# pcie_power.net
KiCad netlist of a schematic drawn in Altium Designer
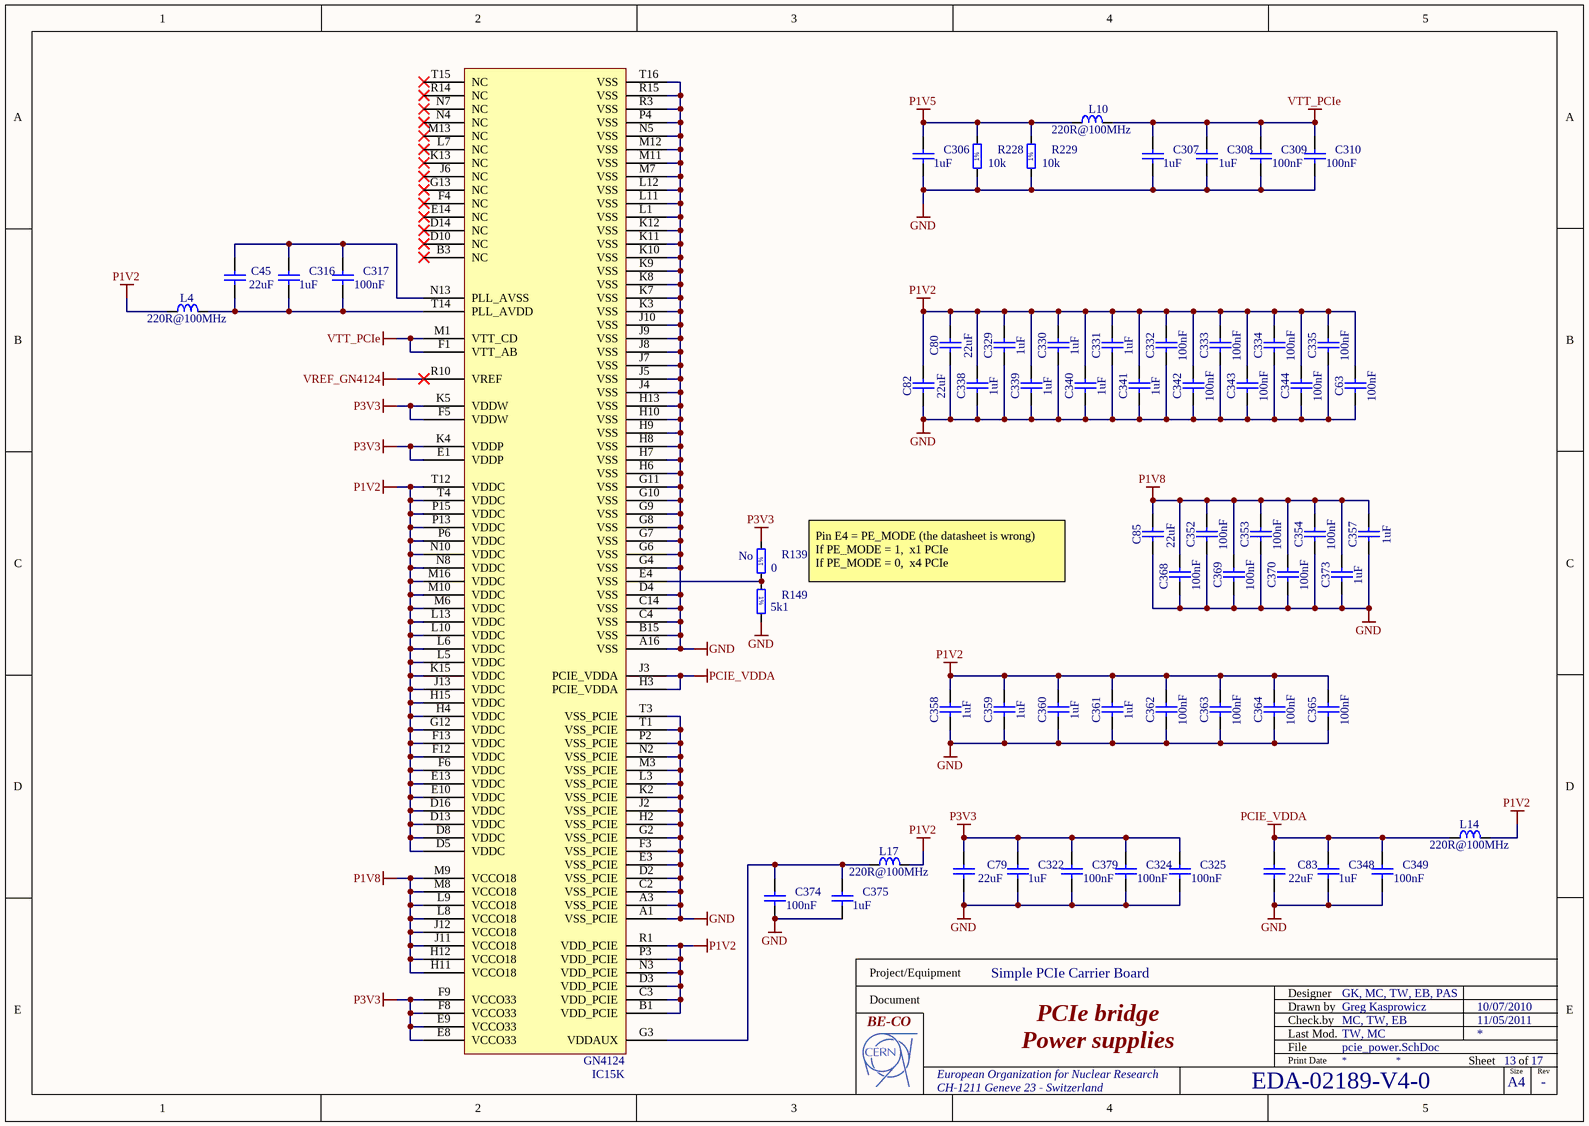
[diagram p0: pcie_power.SchDoc]

(export (version "E")
  (design (tool "Eeschema 10.0.6"))
  (components
    (comp (ref "C45")
      (value "22uF")
      (footprint "CAPC3216X180N")
      (description "Non-polarised capacitor")
      (fields
        (field (name "PART NUMBER") "CC1206_22UF_10V_10%_X7R")
        (field (name "VOLTAGE") "10V")
        (field (name "AUTHOR") "CERN DEM JLC")
      )
      (libsource (lib "Capacitors") (part "Capacitor - non polarized"))
    )
    (comp (ref "C63")
      (value "100nF")
      (footprint "CAPC1005X55N")
      (description "Non-polarised capacitor")
      (fields
        (field (name "PART NUMBER") "CC0402_100NF_16V_10%_X7R")
        (field (name "VOLTAGE") "16V")
        (field (name "AUTHOR") "CERN DEM JLC")
      )
      (libsource (lib "Capacitors") (part "Capacitor - non polarized"))
    )
    (comp (ref "C79")
      (value "22uF")
      (footprint "CAPC3216X180N")
      (description "Non-polarised capacitor")
      (fields
        (field (name "PART NUMBER") "CC1206_22UF_10V_10%_X7R")
        (field (name "VOLTAGE") "10V")
        (field (name "AUTHOR") "CERN DEM JLC")
      )
      (libsource (lib "Capacitors") (part "Capacitor - non polarized"))
    )
    (comp (ref "C80")
      (value "22uF")
      (footprint "CAPC3216X180N")
      (description "Non-polarised capacitor")
      (fields
        (field (name "PART NUMBER") "CC1206_22UF_10V_10%_X7R")
        (field (name "VOLTAGE") "10V")
        (field (name "AUTHOR") "CERN DEM JLC")
      )
      (libsource (lib "Capacitors") (part "Capacitor - non polarized"))
    )
    (comp (ref "C82")
      (value "22uF")
      (footprint "CAPC3216X180N")
      (description "Non-polarised capacitor")
      (fields
        (field (name "PART NUMBER") "CC1206_22UF_10V_10%_X7R")
        (field (name "VOLTAGE") "10V")
        (field (name "AUTHOR") "CERN DEM JLC")
      )
      (libsource (lib "Capacitors") (part "Capacitor - non polarized"))
    )
    (comp (ref "C83")
      (value "22uF")
      (footprint "CAPC3216X180N")
      (description "Non-polarised capacitor")
      (fields
        (field (name "PART NUMBER") "CC1206_22UF_10V_10%_X7R")
        (field (name "VOLTAGE") "10V")
        (field (name "AUTHOR") "CERN DEM JLC")
      )
      (libsource (lib "Capacitors") (part "Capacitor - non polarized"))
    )
    (comp (ref "C85")
      (value "22uF")
      (footprint "CAPC3216X180N")
      (description "Non-polarised capacitor")
      (fields
        (field (name "PART NUMBER") "CC1206_22UF_10V_10%_X7R")
        (field (name "VOLTAGE") "10V")
        (field (name "AUTHOR") "CERN DEM JLC")
      )
      (libsource (lib "Capacitors") (part "Capacitor - non polarized"))
    )
    (comp (ref "C306")
      (value "1uF")
      (footprint "CAPC1608X87N")
      (description "Non-polarised capacitor")
      (fields
        (field (name "PART NUMBER") "CC0603_1UF_16V_10%_X7R")
        (field (name "VOLTAGE") "16V")
        (field (name "AUTHOR") "CERN DEM JLC")
      )
      (libsource (lib "Capacitors") (part "Capacitor - non polarized"))
    )
    (comp (ref "C307")
      (value "1uF")
      (footprint "CAPC1608X87N")
      (description "Non-polarised capacitor")
      (fields
        (field (name "PART NUMBER") "CC0603_1UF_16V_10%_X7R")
        (field (name "VOLTAGE") "16V")
        (field (name "AUTHOR") "CERN DEM JLC")
      )
      (libsource (lib "Capacitors") (part "Capacitor - non polarized"))
    )
    (comp (ref "C308")
      (value "1uF")
      (footprint "CAPC1608X87N")
      (description "Non-polarised capacitor")
      (fields
        (field (name "PART NUMBER") "CC0603_1UF_16V_10%_X7R")
        (field (name "VOLTAGE") "16V")
        (field (name "AUTHOR") "CERN DEM JLC")
      )
      (libsource (lib "Capacitors") (part "Capacitor - non polarized"))
    )
    (comp (ref "C309")
      (value "100nF")
      (footprint "CAPC1005X55N")
      (description "Non-polarised capacitor")
      (fields
        (field (name "PART NUMBER") "CC0402_100NF_16V_10%_X7R")
        (field (name "VOLTAGE") "16V")
        (field (name "AUTHOR") "CERN DEM JLC")
      )
      (libsource (lib "Capacitors") (part "Capacitor - non polarized"))
    )
    (comp (ref "C310")
      (value "100nF")
      (footprint "CAPC1005X55N")
      (description "Non-polarised capacitor")
      (fields
        (field (name "PART NUMBER") "CC0402_100NF_16V_10%_X7R")
        (field (name "VOLTAGE") "16V")
        (field (name "AUTHOR") "CERN DEM JLC")
      )
      (libsource (lib "Capacitors") (part "Capacitor - non polarized"))
    )
    (comp (ref "C316")
      (value "1uF")
      (footprint "CAPC1608X87N")
      (description "Non-polarised capacitor")
      (fields
        (field (name "PART NUMBER") "CC0603_1UF_16V_10%_X7R")
        (field (name "VOLTAGE") "16V")
        (field (name "AUTHOR") "CERN DEM JLC")
      )
      (libsource (lib "Capacitors") (part "Capacitor - non polarized"))
    )
    (comp (ref "C317")
      (value "100nF")
      (footprint "CAPC1005X55N")
      (description "Non-polarised capacitor")
      (fields
        (field (name "PART NUMBER") "CC0402_100NF_16V_10%_X7R")
        (field (name "VOLTAGE") "16V")
        (field (name "AUTHOR") "CERN DEM JLC")
      )
      (libsource (lib "Capacitors") (part "Capacitor - non polarized"))
    )
    (comp (ref "C322")
      (value "1uF")
      (footprint "CAPC1608X87N")
      (description "Non-polarised capacitor")
      (fields
        (field (name "PART NUMBER") "CC0603_1UF_16V_10%_X7R")
        (field (name "VOLTAGE") "16V")
        (field (name "AUTHOR") "CERN DEM JLC")
      )
      (libsource (lib "Capacitors") (part "Capacitor - non polarized"))
    )
    (comp (ref "C324")
      (value "100nF")
      (footprint "CAPC1005X55N")
      (description "Non-polarised capacitor")
      (fields
        (field (name "PART NUMBER") "CC0402_100NF_16V_10%_X7R")
        (field (name "VOLTAGE") "16V")
        (field (name "AUTHOR") "CERN DEM JLC")
      )
      (libsource (lib "Capacitors") (part "Capacitor - non polarized"))
    )
    (comp (ref "C325")
      (value "100nF")
      (footprint "CAPC1005X55N")
      (description "Non-polarised capacitor")
      (fields
        (field (name "PART NUMBER") "CC0402_100NF_16V_10%_X7R")
        (field (name "VOLTAGE") "16V")
        (field (name "AUTHOR") "CERN DEM JLC")
      )
      (libsource (lib "Capacitors") (part "Capacitor - non polarized"))
    )
    (comp (ref "C329")
      (value "1uF")
      (footprint "CAPC1608X87N")
      (description "Non-polarised capacitor")
      (fields
        (field (name "PART NUMBER") "CC0603_1UF_16V_10%_X7R")
        (field (name "VOLTAGE") "16V")
        (field (name "AUTHOR") "CERN DEM JLC")
      )
      (libsource (lib "Capacitors") (part "Capacitor - non polarized"))
    )
    (comp (ref "C330")
      (value "1uF")
      (footprint "CAPC1608X87N")
      (description "Non-polarised capacitor")
      (fields
        (field (name "PART NUMBER") "CC0603_1UF_16V_10%_X7R")
        (field (name "VOLTAGE") "16V")
        (field (name "AUTHOR") "CERN DEM JLC")
      )
      (libsource (lib "Capacitors") (part "Capacitor - non polarized"))
    )
    (comp (ref "C331")
      (value "1uF")
      (footprint "CAPC1608X87N")
      (description "Non-polarised capacitor")
      (fields
        (field (name "PART NUMBER") "CC0603_1UF_16V_10%_X7R")
        (field (name "VOLTAGE") "16V")
        (field (name "AUTHOR") "CERN DEM JLC")
      )
      (libsource (lib "Capacitors") (part "Capacitor - non polarized"))
    )
    (comp (ref "C332")
      (value "100nF")
      (footprint "CAPC1005X55N")
      (description "Non-polarised capacitor")
      (fields
        (field (name "PART NUMBER") "CC0402_100NF_16V_10%_X7R")
        (field (name "VOLTAGE") "16V")
        (field (name "AUTHOR") "CERN DEM JLC")
      )
      (libsource (lib "Capacitors") (part "Capacitor - non polarized"))
    )
    (comp (ref "C333")
      (value "100nF")
      (footprint "CAPC1005X55N")
      (description "Non-polarised capacitor")
      (fields
        (field (name "PART NUMBER") "CC0402_100NF_16V_10%_X7R")
        (field (name "VOLTAGE") "16V")
        (field (name "AUTHOR") "CERN DEM JLC")
      )
      (libsource (lib "Capacitors") (part "Capacitor - non polarized"))
    )
    (comp (ref "C334")
      (value "100nF")
      (footprint "CAPC1005X55N")
      (description "Non-polarised capacitor")
      (fields
        (field (name "PART NUMBER") "CC0402_100NF_16V_10%_X7R")
        (field (name "VOLTAGE") "16V")
        (field (name "AUTHOR") "CERN DEM JLC")
      )
      (libsource (lib "Capacitors") (part "Capacitor - non polarized"))
    )
    (comp (ref "C335")
      (value "100nF")
      (footprint "CAPC1005X55N")
      (description "Non-polarised capacitor")
      (fields
        (field (name "PART NUMBER") "CC0402_100NF_16V_10%_X7R")
        (field (name "VOLTAGE") "16V")
        (field (name "AUTHOR") "CERN DEM JLC")
      )
      (libsource (lib "Capacitors") (part "Capacitor - non polarized"))
    )
    (comp (ref "C338")
      (value "1uF")
      (footprint "CAPC1608X87N")
      (description "Non-polarised capacitor")
      (fields
        (field (name "PART NUMBER") "CC0603_1UF_16V_10%_X7R")
        (field (name "VOLTAGE") "16V")
        (field (name "AUTHOR") "CERN DEM JLC")
      )
      (libsource (lib "Capacitors") (part "Capacitor - non polarized"))
    )
    (comp (ref "C339")
      (value "1uF")
      (footprint "CAPC1608X87N")
      (description "Non-polarised capacitor")
      (fields
        (field (name "PART NUMBER") "CC0603_1UF_16V_10%_X7R")
        (field (name "VOLTAGE") "16V")
        (field (name "AUTHOR") "CERN DEM JLC")
      )
      (libsource (lib "Capacitors") (part "Capacitor - non polarized"))
    )
    (comp (ref "C340")
      (value "1uF")
      (footprint "CAPC1608X87N")
      (description "Non-polarised capacitor")
      (fields
        (field (name "PART NUMBER") "CC0603_1UF_16V_10%_X7R")
        (field (name "VOLTAGE") "16V")
        (field (name "AUTHOR") "CERN DEM JLC")
      )
      (libsource (lib "Capacitors") (part "Capacitor - non polarized"))
    )
    (comp (ref "C341")
      (value "1uF")
      (footprint "CAPC1608X87N")
      (description "Non-polarised capacitor")
      (fields
        (field (name "PART NUMBER") "CC0603_1UF_16V_10%_X7R")
        (field (name "VOLTAGE") "16V")
        (field (name "AUTHOR") "CERN DEM JLC")
      )
      (libsource (lib "Capacitors") (part "Capacitor - non polarized"))
    )
    (comp (ref "C342")
      (value "100nF")
      (footprint "CAPC1005X55N")
      (description "Non-polarised capacitor")
      (fields
        (field (name "PART NUMBER") "CC0402_100NF_16V_10%_X7R")
        (field (name "VOLTAGE") "16V")
        (field (name "AUTHOR") "CERN DEM JLC")
      )
      (libsource (lib "Capacitors") (part "Capacitor - non polarized"))
    )
    (comp (ref "C343")
      (value "100nF")
      (footprint "CAPC1005X55N")
      (description "Non-polarised capacitor")
      (fields
        (field (name "PART NUMBER") "CC0402_100NF_16V_10%_X7R")
        (field (name "VOLTAGE") "16V")
        (field (name "AUTHOR") "CERN DEM JLC")
      )
      (libsource (lib "Capacitors") (part "Capacitor - non polarized"))
    )
    (comp (ref "C344")
      (value "100nF")
      (footprint "CAPC1005X55N")
      (description "Non-polarised capacitor")
      (fields
        (field (name "PART NUMBER") "CC0402_100NF_16V_10%_X7R")
        (field (name "VOLTAGE") "16V")
        (field (name "AUTHOR") "CERN DEM JLC")
      )
      (libsource (lib "Capacitors") (part "Capacitor - non polarized"))
    )
    (comp (ref "C348")
      (value "1uF")
      (footprint "CAPC1608X87N")
      (description "Non-polarised capacitor")
      (fields
        (field (name "PART NUMBER") "CC0603_1UF_16V_10%_X7R")
        (field (name "VOLTAGE") "16V")
        (field (name "AUTHOR") "CERN DEM JLC")
      )
      (libsource (lib "Capacitors") (part "Capacitor - non polarized"))
    )
    (comp (ref "C349")
      (value "100nF")
      (footprint "CAPC1005X55N")
      (description "Non-polarised capacitor")
      (fields
        (field (name "PART NUMBER") "CC0402_100NF_16V_10%_X7R")
        (field (name "VOLTAGE") "16V")
        (field (name "AUTHOR") "CERN DEM JLC")
      )
      (libsource (lib "Capacitors") (part "Capacitor - non polarized"))
    )
    (comp (ref "C352")
      (value "100nF")
      (footprint "CAPC1005X55N")
      (description "Non-polarised capacitor")
      (fields
        (field (name "PART NUMBER") "CC0402_100NF_16V_10%_X7R")
        (field (name "VOLTAGE") "16V")
        (field (name "AUTHOR") "CERN DEM JLC")
      )
      (libsource (lib "Capacitors") (part "Capacitor - non polarized"))
    )
    (comp (ref "C353")
      (value "100nF")
      (footprint "CAPC1005X55N")
      (description "Non-polarised capacitor")
      (fields
        (field (name "PART NUMBER") "CC0402_100NF_16V_10%_X7R")
        (field (name "VOLTAGE") "16V")
        (field (name "AUTHOR") "CERN DEM JLC")
      )
      (libsource (lib "Capacitors") (part "Capacitor - non polarized"))
    )
    (comp (ref "C354")
      (value "100nF")
      (footprint "CAPC1005X55N")
      (description "Non-polarised capacitor")
      (fields
        (field (name "PART NUMBER") "CC0402_100NF_16V_10%_X7R")
        (field (name "VOLTAGE") "16V")
        (field (name "AUTHOR") "CERN DEM JLC")
      )
      (libsource (lib "Capacitors") (part "Capacitor - non polarized"))
    )
    (comp (ref "C357")
      (value "1uF")
      (footprint "CAPC1608X87N")
      (description "Non-polarised capacitor")
      (fields
        (field (name "PART NUMBER") "CC0603_1UF_16V_10%_X7R")
        (field (name "VOLTAGE") "16V")
        (field (name "AUTHOR") "CERN DEM JLC")
      )
      (libsource (lib "Capacitors") (part "Capacitor - non polarized"))
    )
    (comp (ref "C358")
      (value "1uF")
      (footprint "CAPC1608X87N")
      (description "Non-polarised capacitor")
      (fields
        (field (name "PART NUMBER") "CC0603_1UF_16V_10%_X7R")
        (field (name "VOLTAGE") "16V")
        (field (name "AUTHOR") "CERN DEM JLC")
      )
      (libsource (lib "Capacitors") (part "Capacitor - non polarized"))
    )
    (comp (ref "C359")
      (value "1uF")
      (footprint "CAPC1608X87N")
      (description "Non-polarised capacitor")
      (fields
        (field (name "PART NUMBER") "CC0603_1UF_16V_10%_X7R")
        (field (name "VOLTAGE") "16V")
        (field (name "AUTHOR") "CERN DEM JLC")
      )
      (libsource (lib "Capacitors") (part "Capacitor - non polarized"))
    )
    (comp (ref "C360")
      (value "1uF")
      (footprint "CAPC1608X87N")
      (description "Non-polarised capacitor")
      (fields
        (field (name "PART NUMBER") "CC0603_1UF_16V_10%_X7R")
        (field (name "VOLTAGE") "16V")
        (field (name "AUTHOR") "CERN DEM JLC")
      )
      (libsource (lib "Capacitors") (part "Capacitor - non polarized"))
    )
    (comp (ref "C361")
      (value "1uF")
      (footprint "CAPC1608X87N")
      (description "Non-polarised capacitor")
      (fields
        (field (name "PART NUMBER") "CC0603_1UF_16V_10%_X7R")
        (field (name "VOLTAGE") "16V")
        (field (name "AUTHOR") "CERN DEM JLC")
      )
      (libsource (lib "Capacitors") (part "Capacitor - non polarized"))
    )
    (comp (ref "C362")
      (value "100nF")
      (footprint "CAPC1005X55N")
      (description "Non-polarised capacitor")
      (fields
        (field (name "PART NUMBER") "CC0402_100NF_16V_10%_X7R")
        (field (name "VOLTAGE") "16V")
        (field (name "AUTHOR") "CERN DEM JLC")
      )
      (libsource (lib "Capacitors") (part "Capacitor - non polarized"))
    )
    (comp (ref "C363")
      (value "100nF")
      (footprint "CAPC1005X55N")
      (description "Non-polarised capacitor")
      (fields
        (field (name "PART NUMBER") "CC0402_100NF_16V_10%_X7R")
        (field (name "VOLTAGE") "16V")
        (field (name "AUTHOR") "CERN DEM JLC")
      )
      (libsource (lib "Capacitors") (part "Capacitor - non polarized"))
    )
    (comp (ref "C364")
      (value "100nF")
      (footprint "CAPC1005X55N")
      (description "Non-polarised capacitor")
      (fields
        (field (name "PART NUMBER") "CC0402_100NF_16V_10%_X7R")
        (field (name "VOLTAGE") "16V")
        (field (name "AUTHOR") "CERN DEM JLC")
      )
      (libsource (lib "Capacitors") (part "Capacitor - non polarized"))
    )
    (comp (ref "C365")
      (value "100nF")
      (footprint "CAPC1005X55N")
      (description "Non-polarised capacitor")
      (fields
        (field (name "PART NUMBER") "CC0402_100NF_16V_10%_X7R")
        (field (name "VOLTAGE") "16V")
        (field (name "AUTHOR") "CERN DEM JLC")
      )
      (libsource (lib "Capacitors") (part "Capacitor - non polarized"))
    )
    (comp (ref "C368")
      (value "100nF")
      (footprint "CAPC1005X55N")
      (description "Non-polarised capacitor")
      (fields
        (field (name "PART NUMBER") "CC0402_100NF_16V_10%_X7R")
        (field (name "VOLTAGE") "16V")
        (field (name "AUTHOR") "CERN DEM JLC")
      )
      (libsource (lib "Capacitors") (part "Capacitor - non polarized"))
    )
    (comp (ref "C369")
      (value "100nF")
      (footprint "CAPC1005X55N")
      (description "Non-polarised capacitor")
      (fields
        (field (name "PART NUMBER") "CC0402_100NF_16V_10%_X7R")
        (field (name "VOLTAGE") "16V")
        (field (name "AUTHOR") "CERN DEM JLC")
      )
      (libsource (lib "Capacitors") (part "Capacitor - non polarized"))
    )
    (comp (ref "C370")
      (value "100nF")
      (footprint "CAPC1005X55N")
      (description "Non-polarised capacitor")
      (fields
        (field (name "PART NUMBER") "CC0402_100NF_16V_10%_X7R")
        (field (name "VOLTAGE") "16V")
        (field (name "AUTHOR") "CERN DEM JLC")
      )
      (libsource (lib "Capacitors") (part "Capacitor - non polarized"))
    )
    (comp (ref "C373")
      (value "1uF")
      (footprint "CAPC1608X87N")
      (description "Non-polarised capacitor")
      (fields
        (field (name "PART NUMBER") "CC0603_1UF_16V_10%_X7R")
        (field (name "VOLTAGE") "16V")
        (field (name "AUTHOR") "CERN DEM JLC")
      )
      (libsource (lib "Capacitors") (part "Capacitor - non polarized"))
    )
    (comp (ref "C374")
      (value "100nF")
      (footprint "CAPC1005X55N")
      (description "Non-polarised capacitor")
      (fields
        (field (name "PART NUMBER") "CC0402_100NF_16V_10%_X7R")
        (field (name "VOLTAGE") "16V")
        (field (name "AUTHOR") "CERN DEM JLC")
      )
      (libsource (lib "Capacitors") (part "Capacitor - non polarized"))
    )
    (comp (ref "C375")
      (value "1uF")
      (footprint "CAPC1608X87N")
      (description "Non-polarised capacitor")
      (fields
        (field (name "PART NUMBER") "CC0603_1UF_16V_10%_X7R")
        (field (name "VOLTAGE") "16V")
        (field (name "AUTHOR") "CERN DEM JLC")
      )
      (libsource (lib "Capacitors") (part "Capacitor - non polarized"))
    )
    (comp (ref "C379")
      (value "100nF")
      (footprint "CAPC1005X55N")
      (description "Non-polarised capacitor")
      (fields
        (field (name "PART NUMBER") "CC0402_100NF_16V_10%_X7R")
        (field (name "VOLTAGE") "16V")
        (field (name "AUTHOR") "CERN DEM JLC")
      )
      (libsource (lib "Capacitors") (part "Capacitor - non polarized"))
    )
    (comp (ref "IC15")
      (value "GN4124")
      (footprint "BGA256C100P16X16_1700X1700X150")
      (description "x4 Lane PCI Express to Local Bridge")
      (fields (field (name "MANUFACTURER") "GENNUM") (field (name "AUTHOR") "CERN DEM JLC"))
      (libsource (lib "ICs And Semiconductors") (part "GN4124"))
    )
    (comp (ref "L4")
      (value "220R@100MHz")
      (footprint "INDC2012X105N")
      (description "Inductor")
      (fields
        (field (name "PART NUMBER") "IND0805_MURATA_BLM21PG221SN1D")
        (field (name "POWER") "2A")
        (field (name "AUTHOR") "CERN DEM JLC")
      )
      (libsource (lib "Inductors & Transformers") (part "Inductor"))
    )
    (comp (ref "L10")
      (value "220R@100MHz")
      (footprint "INDC2012X105N")
      (description "Inductor")
      (fields
        (field (name "PART NUMBER") "IND0805_MURATA_BLM21PG221SN1D")
        (field (name "POWER") "2A")
        (field (name "AUTHOR") "CERN DEM JLC")
      )
      (libsource (lib "Inductors & Transformers") (part "Inductor"))
    )
    (comp (ref "L14")
      (value "220R@100MHz")
      (footprint "INDC2012X105N")
      (description "Inductor")
      (fields
        (field (name "PART NUMBER") "IND0805_MURATA_BLM21PG221SN1D")
        (field (name "POWER") "2A")
        (field (name "AUTHOR") "CERN DEM JLC")
      )
      (libsource (lib "Inductors & Transformers") (part "Inductor"))
    )
    (comp (ref "L17")
      (value "220R@100MHz")
      (footprint "INDC2012X105N")
      (description "Inductor")
      (fields
        (field (name "PART NUMBER") "IND0805_MURATA_BLM21PG221SN1D")
        (field (name "POWER") "2A")
        (field (name "AUTHOR") "CERN DEM JLC")
      )
      (libsource (lib "Inductors & Transformers") (part "Inductor"))
    )
    (comp (ref "R139")
      (value "0")
      (footprint "RESC1608X55N")
      (description "Resistor - 1%")
      (fields
        (field (name "PART NUMBER") "R0603_0R_JUMPER")
        (field (name "MANUFACTURER") "GENERIC")
        (field (name "MOUNTED") "No")
        (field (name "AUTHOR") "CERN DEM JLC")
      )
      (libsource (lib "Resistors") (part "Resistor - 1%"))
    )
    (comp (ref "R149")
      (value "5k1")
      (footprint "RESC1608X55N")
      (description "Resistor - 1%")
      (fields
        (field (name "PART NUMBER") "R0603_5K1_1%_0.1W_100PPM")
        (field (name "POWER") "0.1W")
        (field (name "AUTHOR") "CERN DEM JLC")
      )
      (libsource (lib "Resistors") (part "Resistor - 1%"))
    )
    (comp (ref "R228")
      (value "10k")
      (footprint "RESC1608X55N")
      (description "Resistor - 1%")
      (fields
        (field (name "PART NUMBER") "R0603_10K_1%_0.1W_100PPM")
        (field (name "POWER") "0.1W")
        (field (name "AUTHOR") "CERN DEM JLC")
      )
      (libsource (lib "Resistors") (part "Resistor - 1%"))
    )
    (comp (ref "R229")
      (value "10k")
      (footprint "RESC1608X55N")
      (description "Resistor - 1%")
      (fields
        (field (name "PART NUMBER") "R0603_10K_1%_0.1W_100PPM")
        (field (name "POWER") "0.1W")
        (field (name "AUTHOR") "CERN DEM JLC")
      )
      (libsource (lib "Resistors") (part "Resistor - 1%"))
    )
  )
  (nets
    (net (code "1") (name "GND") (class "Default")
      (node (ref "C306") (pin "1") (pinfunction "1_1") (pintype "passive"))
      (node (ref "C307") (pin "1") (pinfunction "1_1") (pintype "passive"))
      (node (ref "C308") (pin "1") (pinfunction "1_1") (pintype "passive"))
      (node (ref "C309") (pin "1") (pinfunction "1_1") (pintype "passive"))
      (node (ref "C310") (pin "1") (pinfunction "1_1") (pintype "passive"))
      (node (ref "C322") (pin "1") (pinfunction "1_1") (pintype "passive"))
      (node (ref "C324") (pin "1") (pinfunction "1_1") (pintype "passive"))
      (node (ref "C325") (pin "1") (pinfunction "1_1") (pintype "passive"))
      (node (ref "C329") (pin "1") (pinfunction "1_1") (pintype "passive"))
      (node (ref "C330") (pin "1") (pinfunction "1_1") (pintype "passive"))
      (node (ref "C331") (pin "1") (pinfunction "1_1") (pintype "passive"))
      (node (ref "C332") (pin "1") (pinfunction "1_1") (pintype "passive"))
      (node (ref "C333") (pin "1") (pinfunction "1_1") (pintype "passive"))
      (node (ref "C334") (pin "1") (pinfunction "1_1") (pintype "passive"))
      (node (ref "C335") (pin "1") (pinfunction "1_1") (pintype "passive"))
      (node (ref "C338") (pin "1") (pinfunction "1_1") (pintype "passive"))
      (node (ref "C339") (pin "1") (pinfunction "1_1") (pintype "passive"))
      (node (ref "C340") (pin "1") (pinfunction "1_1") (pintype "passive"))
      (node (ref "C341") (pin "1") (pinfunction "1_1") (pintype "passive"))
      (node (ref "C342") (pin "1") (pinfunction "1_1") (pintype "passive"))
      (node (ref "C343") (pin "1") (pinfunction "1_1") (pintype "passive"))
      (node (ref "C344") (pin "1") (pinfunction "1_1") (pintype "passive"))
      (node (ref "C348") (pin "1") (pinfunction "1_1") (pintype "passive"))
      (node (ref "C349") (pin "1") (pinfunction "1_1") (pintype "passive"))
      (node (ref "C352") (pin "1") (pinfunction "1_1") (pintype "passive"))
      (node (ref "C353") (pin "1") (pinfunction "1_1") (pintype "passive"))
      (node (ref "C354") (pin "1") (pinfunction "1_1") (pintype "passive"))
      (node (ref "C357") (pin "1") (pinfunction "1_1") (pintype "passive"))
      (node (ref "C358") (pin "1") (pinfunction "1_1") (pintype "passive"))
      (node (ref "C359") (pin "1") (pinfunction "1_1") (pintype "passive"))
      (node (ref "C360") (pin "1") (pinfunction "1_1") (pintype "passive"))
      (node (ref "C361") (pin "1") (pinfunction "1_1") (pintype "passive"))
      (node (ref "C362") (pin "1") (pinfunction "1_1") (pintype "passive"))
      (node (ref "C363") (pin "1") (pinfunction "1_1") (pintype "passive"))
      (node (ref "C364") (pin "1") (pinfunction "1_1") (pintype "passive"))
      (node (ref "C365") (pin "1") (pinfunction "1_1") (pintype "passive"))
      (node (ref "C368") (pin "2") (pinfunction "2_2") (pintype "passive"))
      (node (ref "C369") (pin "1") (pinfunction "1_1") (pintype "passive"))
      (node (ref "C370") (pin "1") (pinfunction "1_1") (pintype "passive"))
      (node (ref "C373") (pin "1") (pinfunction "1_1") (pintype "passive"))
      (node (ref "C374") (pin "1") (pinfunction "1_1") (pintype "passive"))
      (node (ref "C375") (pin "1") (pinfunction "1_1") (pintype "passive"))
      (node (ref "C379") (pin "1") (pinfunction "1_1") (pintype "passive"))
      (node (ref "C63") (pin "1") (pinfunction "1_1") (pintype "passive"))
      (node (ref "C79") (pin "1") (pinfunction "1_1") (pintype "passive"))
      (node (ref "C80") (pin "1") (pinfunction "1_1") (pintype "passive"))
      (node (ref "C82") (pin "1") (pinfunction "1_1") (pintype "passive"))
      (node (ref "C83") (pin "1") (pinfunction "1_1") (pintype "passive"))
      (node (ref "C85") (pin "1") (pinfunction "1_1") (pintype "passive"))
      (node (ref "IC15") (pin "A1") (pinfunction "VSS_PCIE_A1") (pintype "power_in"))
      (node (ref "IC15") (pin "A16") (pinfunction "VSS_A16") (pintype "power_in"))
      (node (ref "IC15") (pin "A3") (pinfunction "VSS_PCIE_A3") (pintype "power_in"))
      (node (ref "IC15") (pin "B15") (pinfunction "VSS_B15") (pintype "power_in"))
      (node (ref "IC15") (pin "C14") (pinfunction "VSS_C14") (pintype "power_in"))
      (node (ref "IC15") (pin "C2") (pinfunction "VSS_PCIE_C2") (pintype "power_in"))
      (node (ref "IC15") (pin "C4") (pinfunction "VSS_C4") (pintype "power_in"))
      (node (ref "IC15") (pin "D2") (pinfunction "VSS_PCIE_D2") (pintype "power_in"))
      (node (ref "IC15") (pin "D4") (pinfunction "VSS_D4") (pintype "power_in"))
      (node (ref "IC15") (pin "E3") (pinfunction "VSS_PCIE_E3") (pintype "power_in"))
      (node (ref "IC15") (pin "F3") (pinfunction "VSS_PCIE_F3") (pintype "power_in"))
      (node (ref "IC15") (pin "G10") (pinfunction "VSS_G10") (pintype "power_in"))
      (node (ref "IC15") (pin "G11") (pinfunction "VSS_G11") (pintype "power_in"))
      (node (ref "IC15") (pin "G2") (pinfunction "VSS_PCIE_G2") (pintype "power_in"))
      (node (ref "IC15") (pin "G4") (pinfunction "VSS_G4") (pintype "power_in"))
      (node (ref "IC15") (pin "G6") (pinfunction "VSS_G6") (pintype "power_in"))
      (node (ref "IC15") (pin "G7") (pinfunction "VSS_G7") (pintype "power_in"))
      (node (ref "IC15") (pin "G8") (pinfunction "VSS_G8") (pintype "power_in"))
      (node (ref "IC15") (pin "G9") (pinfunction "VSS_G9") (pintype "power_in"))
      (node (ref "IC15") (pin "H10") (pinfunction "VSS_H10") (pintype "power_in"))
      (node (ref "IC15") (pin "H13") (pinfunction "VSS_H13") (pintype "power_in"))
      (node (ref "IC15") (pin "H2") (pinfunction "VSS_PCIE_H2") (pintype "power_in"))
      (node (ref "IC15") (pin "H6") (pinfunction "VSS_H6") (pintype "power_in"))
      (node (ref "IC15") (pin "H7") (pinfunction "VSS_H7") (pintype "power_in"))
      (node (ref "IC15") (pin "H8") (pinfunction "VSS_H8") (pintype "power_in"))
      (node (ref "IC15") (pin "H9") (pinfunction "VSS_H9") (pintype "power_in"))
      (node (ref "IC15") (pin "J10") (pinfunction "VSS_J10") (pintype "power_in"))
      (node (ref "IC15") (pin "J2") (pinfunction "VSS_PCIE_J2") (pintype "power_in"))
      (node (ref "IC15") (pin "J4") (pinfunction "VSS_J4") (pintype "power_in"))
      (node (ref "IC15") (pin "J5") (pinfunction "VSS_J5") (pintype "power_in"))
      (node (ref "IC15") (pin "J7") (pinfunction "VSS_J7") (pintype "power_in"))
      (node (ref "IC15") (pin "J8") (pinfunction "VSS_J8") (pintype "power_in"))
      (node (ref "IC15") (pin "J9") (pinfunction "VSS_J9") (pintype "power_in"))
      (node (ref "IC15") (pin "K10") (pinfunction "VSS_K10") (pintype "power_in"))
      (node (ref "IC15") (pin "K11") (pinfunction "VSS_K11") (pintype "power_in"))
      (node (ref "IC15") (pin "K12") (pinfunction "VSS_K12") (pintype "power_in"))
      (node (ref "IC15") (pin "K2") (pinfunction "VSS_PCIE_K2") (pintype "power_in"))
      (node (ref "IC15") (pin "K3") (pinfunction "VSS_K3") (pintype "power_in"))
      (node (ref "IC15") (pin "K7") (pinfunction "VSS_K7") (pintype "power_in"))
      (node (ref "IC15") (pin "K8") (pinfunction "VSS_K8") (pintype "power_in"))
      (node (ref "IC15") (pin "K9") (pinfunction "VSS_K9") (pintype "power_in"))
      (node (ref "IC15") (pin "L1") (pinfunction "VSS_L1") (pintype "power_in"))
      (node (ref "IC15") (pin "L11") (pinfunction "VSS_L11") (pintype "power_in"))
      (node (ref "IC15") (pin "L12") (pinfunction "VSS_L12") (pintype "power_in"))
      (node (ref "IC15") (pin "L3") (pinfunction "VSS_PCIE_L3") (pintype "power_in"))
      (node (ref "IC15") (pin "M11") (pinfunction "VSS_M11") (pintype "power_in"))
      (node (ref "IC15") (pin "M12") (pinfunction "VSS_M12") (pintype "power_in"))
      (node (ref "IC15") (pin "M3") (pinfunction "VSS_PCIE_M3") (pintype "power_in"))
      (node (ref "IC15") (pin "M7") (pinfunction "VSS_M7") (pintype "power_in"))
      (node (ref "IC15") (pin "N2") (pinfunction "VSS_PCIE_N2") (pintype "power_in"))
      (node (ref "IC15") (pin "N5") (pinfunction "VSS_N5") (pintype "power_in"))
      (node (ref "IC15") (pin "P2") (pinfunction "VSS_PCIE_P2") (pintype "power_in"))
      (node (ref "IC15") (pin "P4") (pinfunction "VSS_P4") (pintype "power_in"))
      (node (ref "IC15") (pin "R15") (pinfunction "VSS_R15") (pintype "power_in"))
      (node (ref "IC15") (pin "R3") (pinfunction "VSS_R3") (pintype "power_in"))
      (node (ref "IC15") (pin "T1") (pinfunction "VSS_PCIE_T1") (pintype "power_in"))
      (node (ref "IC15") (pin "T16") (pinfunction "VSS_T16") (pintype "power_in"))
      (node (ref "IC15") (pin "T3") (pinfunction "VSS_PCIE_T3") (pintype "power_in"))
      (node (ref "R149") (pin "2") (pinfunction "2_2") (pintype "passive"))
      (node (ref "R228") (pin "1") (pinfunction "1_1") (pintype "passive"))
      (node (ref "R229") (pin "1") (pinfunction "1_1") (pintype "passive"))
    )
    (net (code "2") (name "Net-(IC15K-PLL_AVDD)") (class "Default")
      (node (ref "C316") (pin "1") (pinfunction "1_1") (pintype "passive"))
      (node (ref "C317") (pin "1") (pinfunction "1_1") (pintype "passive"))
      (node (ref "C45") (pin "2") (pinfunction "2_2") (pintype "passive"))
      (node (ref "IC15") (pin "T14") (pinfunction "PLL_AVDD_T14") (pintype "power_in"))
      (node (ref "L4") (pin "2") (pinfunction "2_2") (pintype "passive"))
    )
    (net (code "3") (name "Net-(IC15K-PLL_AVSS)") (class "Default")
      (node (ref "C316") (pin "2") (pinfunction "2_2") (pintype "passive"))
      (node (ref "C317") (pin "2") (pinfunction "2_2") (pintype "passive"))
      (node (ref "C45") (pin "1") (pinfunction "1_1") (pintype "passive"))
      (node (ref "IC15") (pin "N13") (pinfunction "PLL_AVSS_N13") (pintype "power_in"))
    )
    (net (code "4") (name "Net-(IC15K-VDDAUX)") (class "Default")
      (node (ref "C374") (pin "2") (pinfunction "2_2") (pintype "passive"))
      (node (ref "C375") (pin "2") (pinfunction "2_2") (pintype "passive"))
      (node (ref "IC15") (pin "G3") (pinfunction "VDDAUX_G3") (pintype "power_in"))
      (node (ref "L17") (pin "1") (pinfunction "1_1") (pintype "passive"))
    )
    (net (code "5") (name "Net-(IC15K-VSS-PadE4)") (class "Default")
      (node (ref "IC15") (pin "E4") (pinfunction "VSS_E4") (pintype "power_in"))
      (node (ref "R139") (pin "1") (pinfunction "1_1") (pintype "passive"))
      (node (ref "R149") (pin "1") (pinfunction "1_1") (pintype "passive"))
    )
    (net (code "6") (name "P1V2") (class "Default")
      (node (ref "C329") (pin "2") (pinfunction "2_2") (pintype "passive"))
      (node (ref "C330") (pin "2") (pinfunction "2_2") (pintype "passive"))
      (node (ref "C331") (pin "2") (pinfunction "2_2") (pintype "passive"))
      (node (ref "C332") (pin "2") (pinfunction "2_2") (pintype "passive"))
      (node (ref "C333") (pin "2") (pinfunction "2_2") (pintype "passive"))
      (node (ref "C334") (pin "2") (pinfunction "2_2") (pintype "passive"))
      (node (ref "C335") (pin "2") (pinfunction "2_2") (pintype "passive"))
      (node (ref "C338") (pin "2") (pinfunction "2_2") (pintype "passive"))
      (node (ref "C339") (pin "2") (pinfunction "2_2") (pintype "passive"))
      (node (ref "C340") (pin "2") (pinfunction "2_2") (pintype "passive"))
      (node (ref "C341") (pin "2") (pinfunction "2_2") (pintype "passive"))
      (node (ref "C342") (pin "2") (pinfunction "2_2") (pintype "passive"))
      (node (ref "C343") (pin "2") (pinfunction "2_2") (pintype "passive"))
      (node (ref "C344") (pin "2") (pinfunction "2_2") (pintype "passive"))
      (node (ref "C358") (pin "2") (pinfunction "2_2") (pintype "passive"))
      (node (ref "C359") (pin "2") (pinfunction "2_2") (pintype "passive"))
      (node (ref "C360") (pin "2") (pinfunction "2_2") (pintype "passive"))
      (node (ref "C361") (pin "2") (pinfunction "2_2") (pintype "passive"))
      (node (ref "C362") (pin "2") (pinfunction "2_2") (pintype "passive"))
      (node (ref "C363") (pin "2") (pinfunction "2_2") (pintype "passive"))
      (node (ref "C364") (pin "2") (pinfunction "2_2") (pintype "passive"))
      (node (ref "C365") (pin "2") (pinfunction "2_2") (pintype "passive"))
      (node (ref "C63") (pin "2") (pinfunction "2_2") (pintype "passive"))
      (node (ref "C80") (pin "2") (pinfunction "2_2") (pintype "passive"))
      (node (ref "C82") (pin "2") (pinfunction "2_2") (pintype "passive"))
      (node (ref "IC15") (pin "B1") (pinfunction "VDD_PCIE_B1") (pintype "power_in"))
      (node (ref "IC15") (pin "C3") (pinfunction "VDD_PCIE_C3") (pintype "power_in"))
      (node (ref "IC15") (pin "D13") (pinfunction "VDDC_D13") (pintype "power_in"))
      (node (ref "IC15") (pin "D16") (pinfunction "VDDC_D16") (pintype "power_in"))
      (node (ref "IC15") (pin "D3") (pinfunction "VDD_PCIE_D3") (pintype "power_in"))
      (node (ref "IC15") (pin "D5") (pinfunction "VDDC_D5") (pintype "power_in"))
      (node (ref "IC15") (pin "D8") (pinfunction "VDDC_D8") (pintype "power_in"))
      (node (ref "IC15") (pin "E10") (pinfunction "VDDC_E10") (pintype "power_in"))
      (node (ref "IC15") (pin "E13") (pinfunction "VDDC_E13") (pintype "power_in"))
      (node (ref "IC15") (pin "F12") (pinfunction "VDDC_F12") (pintype "power_in"))
      (node (ref "IC15") (pin "F13") (pinfunction "VDDC_F13") (pintype "power_in"))
      (node (ref "IC15") (pin "F6") (pinfunction "VDDC_F6") (pintype "power_in"))
      (node (ref "IC15") (pin "G12") (pinfunction "VDDC_G12") (pintype "power_in"))
      (node (ref "IC15") (pin "H15") (pinfunction "VDDC_H15") (pintype "power_in"))
      (node (ref "IC15") (pin "H4") (pinfunction "VDDC_H4") (pintype "power_in"))
      (node (ref "IC15") (pin "J13") (pinfunction "VDDC_J13") (pintype "power_in"))
      (node (ref "IC15") (pin "K15") (pinfunction "VDDC_K15") (pintype "power_in"))
      (node (ref "IC15") (pin "L10") (pinfunction "VDDC_L10") (pintype "power_in"))
      (node (ref "IC15") (pin "L13") (pinfunction "VDDC_L13") (pintype "power_in"))
      (node (ref "IC15") (pin "L5") (pinfunction "VDDC_L5") (pintype "power_in"))
      (node (ref "IC15") (pin "L6") (pinfunction "VDDC_L6") (pintype "power_in"))
      (node (ref "IC15") (pin "M10") (pinfunction "VDDC_M10") (pintype "power_in"))
      (node (ref "IC15") (pin "M16") (pinfunction "VDDC_M16") (pintype "power_in"))
      (node (ref "IC15") (pin "M6") (pinfunction "VDDC_M6") (pintype "power_in"))
      (node (ref "IC15") (pin "N10") (pinfunction "VDDC_N10") (pintype "power_in"))
      (node (ref "IC15") (pin "N3") (pinfunction "VDD_PCIE_N3") (pintype "power_in"))
      (node (ref "IC15") (pin "N8") (pinfunction "VDDC_N8") (pintype "power_in"))
      (node (ref "IC15") (pin "P13") (pinfunction "VDDC_P13") (pintype "power_in"))
      (node (ref "IC15") (pin "P15") (pinfunction "VDDC_P15") (pintype "power_in"))
      (node (ref "IC15") (pin "P3") (pinfunction "VDD_PCIE_P3") (pintype "power_in"))
      (node (ref "IC15") (pin "P6") (pinfunction "VDDC_P6") (pintype "power_in"))
      (node (ref "IC15") (pin "R1") (pinfunction "VDD_PCIE_R1") (pintype "power_in"))
      (node (ref "IC15") (pin "T12") (pinfunction "VDDC_T12") (pintype "power_in"))
      (node (ref "IC15") (pin "T4") (pinfunction "VDDC_T4") (pintype "power_in"))
      (node (ref "L14") (pin "2") (pinfunction "2_2") (pintype "passive"))
      (node (ref "L17") (pin "2") (pinfunction "2_2") (pintype "passive"))
      (node (ref "L4") (pin "1") (pinfunction "1_1") (pintype "passive"))
    )
    (net (code "7") (name "P1V5") (class "Default")
      (node (ref "C306") (pin "2") (pinfunction "2_2") (pintype "passive"))
      (node (ref "L10") (pin "1") (pinfunction "1_1") (pintype "passive"))
      (node (ref "R228") (pin "2") (pinfunction "2_2") (pintype "passive"))
      (node (ref "R229") (pin "2") (pinfunction "2_2") (pintype "passive"))
    )
    (net (code "8") (name "P1V8") (class "Default")
      (node (ref "C352") (pin "2") (pinfunction "2_2") (pintype "passive"))
      (node (ref "C353") (pin "2") (pinfunction "2_2") (pintype "passive"))
      (node (ref "C354") (pin "2") (pinfunction "2_2") (pintype "passive"))
      (node (ref "C357") (pin "2") (pinfunction "2_2") (pintype "passive"))
      (node (ref "C368") (pin "1") (pinfunction "1_1") (pintype "passive"))
      (node (ref "C369") (pin "2") (pinfunction "2_2") (pintype "passive"))
      (node (ref "C370") (pin "2") (pinfunction "2_2") (pintype "passive"))
      (node (ref "C373") (pin "2") (pinfunction "2_2") (pintype "passive"))
      (node (ref "C85") (pin "2") (pinfunction "2_2") (pintype "passive"))
      (node (ref "IC15") (pin "H11") (pinfunction "VCCO18_H11") (pintype "power_in"))
      (node (ref "IC15") (pin "H12") (pinfunction "VCCO18_H12") (pintype "power_in"))
      (node (ref "IC15") (pin "J11") (pinfunction "VCCO18_J11") (pintype "power_in"))
      (node (ref "IC15") (pin "J12") (pinfunction "VCCO18_J12") (pintype "power_in"))
      (node (ref "IC15") (pin "L8") (pinfunction "VCCO18_L8") (pintype "power_in"))
      (node (ref "IC15") (pin "L9") (pinfunction "VCCO18_L9") (pintype "power_in"))
      (node (ref "IC15") (pin "M8") (pinfunction "VCCO18_M8") (pintype "power_in"))
      (node (ref "IC15") (pin "M9") (pinfunction "VCCO18_M9") (pintype "power_in"))
    )
    (net (code "9") (name "P3V3") (class "Default")
      (node (ref "C322") (pin "2") (pinfunction "2_2") (pintype "passive"))
      (node (ref "C324") (pin "2") (pinfunction "2_2") (pintype "passive"))
      (node (ref "C325") (pin "2") (pinfunction "2_2") (pintype "passive"))
      (node (ref "C379") (pin "2") (pinfunction "2_2") (pintype "passive"))
      (node (ref "C79") (pin "2") (pinfunction "2_2") (pintype "passive"))
      (node (ref "IC15") (pin "E1") (pinfunction "VDDP_E1") (pintype "power_in"))
      (node (ref "IC15") (pin "E8") (pinfunction "VCCO33_E8") (pintype "power_in"))
      (node (ref "IC15") (pin "E9") (pinfunction "VCCO33_E9") (pintype "power_in"))
      (node (ref "IC15") (pin "F5") (pinfunction "VDDW_F5") (pintype "power_in"))
      (node (ref "IC15") (pin "F8") (pinfunction "VCCO33_F8") (pintype "power_in"))
      (node (ref "IC15") (pin "F9") (pinfunction "VCCO33_F9") (pintype "power_in"))
      (node (ref "IC15") (pin "K4") (pinfunction "VDDP_K4") (pintype "power_in"))
      (node (ref "IC15") (pin "K5") (pinfunction "VDDW_K5") (pintype "power_in"))
      (node (ref "R139") (pin "2") (pinfunction "2_2") (pintype "passive"))
    )
    (net (code "10") (name "PCIE_VDDA") (class "Default")
      (node (ref "C348") (pin "2") (pinfunction "2_2") (pintype "passive"))
      (node (ref "C349") (pin "2") (pinfunction "2_2") (pintype "passive"))
      (node (ref "C83") (pin "2") (pinfunction "2_2") (pintype "passive"))
      (node (ref "IC15") (pin "H3") (pinfunction "PCIE_VDDA_H3") (pintype "power_in"))
      (node (ref "IC15") (pin "J3") (pinfunction "PCIE_VDDA_J3") (pintype "power_in"))
      (node (ref "L14") (pin "1") (pinfunction "1_1") (pintype "passive"))
    )
    (net (code "11") (name "VREF_GN4124") (class "Default")
      (node (ref "IC15") (pin "R10") (pinfunction "VREF_R10") (pintype "power_in"))
    )
    (net (code "12") (name "VTT_PCIe") (class "Default")
      (node (ref "C307") (pin "2") (pinfunction "2_2") (pintype "passive"))
      (node (ref "C308") (pin "2") (pinfunction "2_2") (pintype "passive"))
      (node (ref "C309") (pin "2") (pinfunction "2_2") (pintype "passive"))
      (node (ref "C310") (pin "2") (pinfunction "2_2") (pintype "passive"))
      (node (ref "IC15") (pin "F1") (pinfunction "VTT_AB_F1") (pintype "power_in"))
      (node (ref "IC15") (pin "M1") (pinfunction "VTT_CD_M1") (pintype "power_in"))
      (node (ref "L10") (pin "2") (pinfunction "2_2") (pintype "passive"))
    )
    (net (code "13") (name "unconnected-(IC15K-NC-PadB3)") (class "Default")
      (node (ref "IC15") (pin "B3") (pinfunction "NC_B3") (pintype "passive+no_connect"))
    )
    (net (code "14") (name "unconnected-(IC15K-NC-PadD10)") (class "Default")
      (node (ref "IC15") (pin "D10") (pinfunction "NC_D10") (pintype "passive+no_connect"))
    )
    (net (code "15") (name "unconnected-(IC15K-NC-PadD14)") (class "Default")
      (node (ref "IC15") (pin "D14") (pinfunction "NC_D14") (pintype "passive+no_connect"))
    )
    (net (code "16") (name "unconnected-(IC15K-NC-PadE14)") (class "Default")
      (node (ref "IC15") (pin "E14") (pinfunction "NC_E14") (pintype "passive+no_connect"))
    )
    (net (code "17") (name "unconnected-(IC15K-NC-PadF4)") (class "Default")
      (node (ref "IC15") (pin "F4") (pinfunction "NC_F4") (pintype "passive+no_connect"))
    )
    (net (code "18") (name "unconnected-(IC15K-NC-PadG13)") (class "Default")
      (node (ref "IC15") (pin "G13") (pinfunction "NC_G13") (pintype "passive+no_connect"))
    )
    (net (code "19") (name "unconnected-(IC15K-NC-PadJ6)") (class "Default")
      (node (ref "IC15") (pin "J6") (pinfunction "NC_J6") (pintype "passive+no_connect"))
    )
    (net (code "20") (name "unconnected-(IC15K-NC-PadK13)") (class "Default")
      (node (ref "IC15") (pin "K13") (pinfunction "NC_K13") (pintype "passive+no_connect"))
    )
    (net (code "21") (name "unconnected-(IC15K-NC-PadL7)") (class "Default")
      (node (ref "IC15") (pin "L7") (pinfunction "NC_L7") (pintype "passive+no_connect"))
    )
    (net (code "22") (name "unconnected-(IC15K-NC-PadM13)") (class "Default")
      (node (ref "IC15") (pin "M13") (pinfunction "NC_M13") (pintype "passive+no_connect"))
    )
    (net (code "23") (name "unconnected-(IC15K-NC-PadN4)") (class "Default")
      (node (ref "IC15") (pin "N4") (pinfunction "NC_N4") (pintype "passive+no_connect"))
    )
    (net (code "24") (name "unconnected-(IC15K-NC-PadN7)") (class "Default")
      (node (ref "IC15") (pin "N7") (pinfunction "NC_N7") (pintype "passive+no_connect"))
    )
    (net (code "25") (name "unconnected-(IC15K-NC-PadR14)") (class "Default")
      (node (ref "IC15") (pin "R14") (pinfunction "NC_R14") (pintype "passive+no_connect"))
    )
    (net (code "26") (name "unconnected-(IC15K-NC-PadT15)") (class "Default")
      (node (ref "IC15") (pin "T15") (pinfunction "NC_T15") (pintype "passive+no_connect"))
    )
  )
)
